# appleii.net
KiCad netlist of a schematic drawn in EAGLE
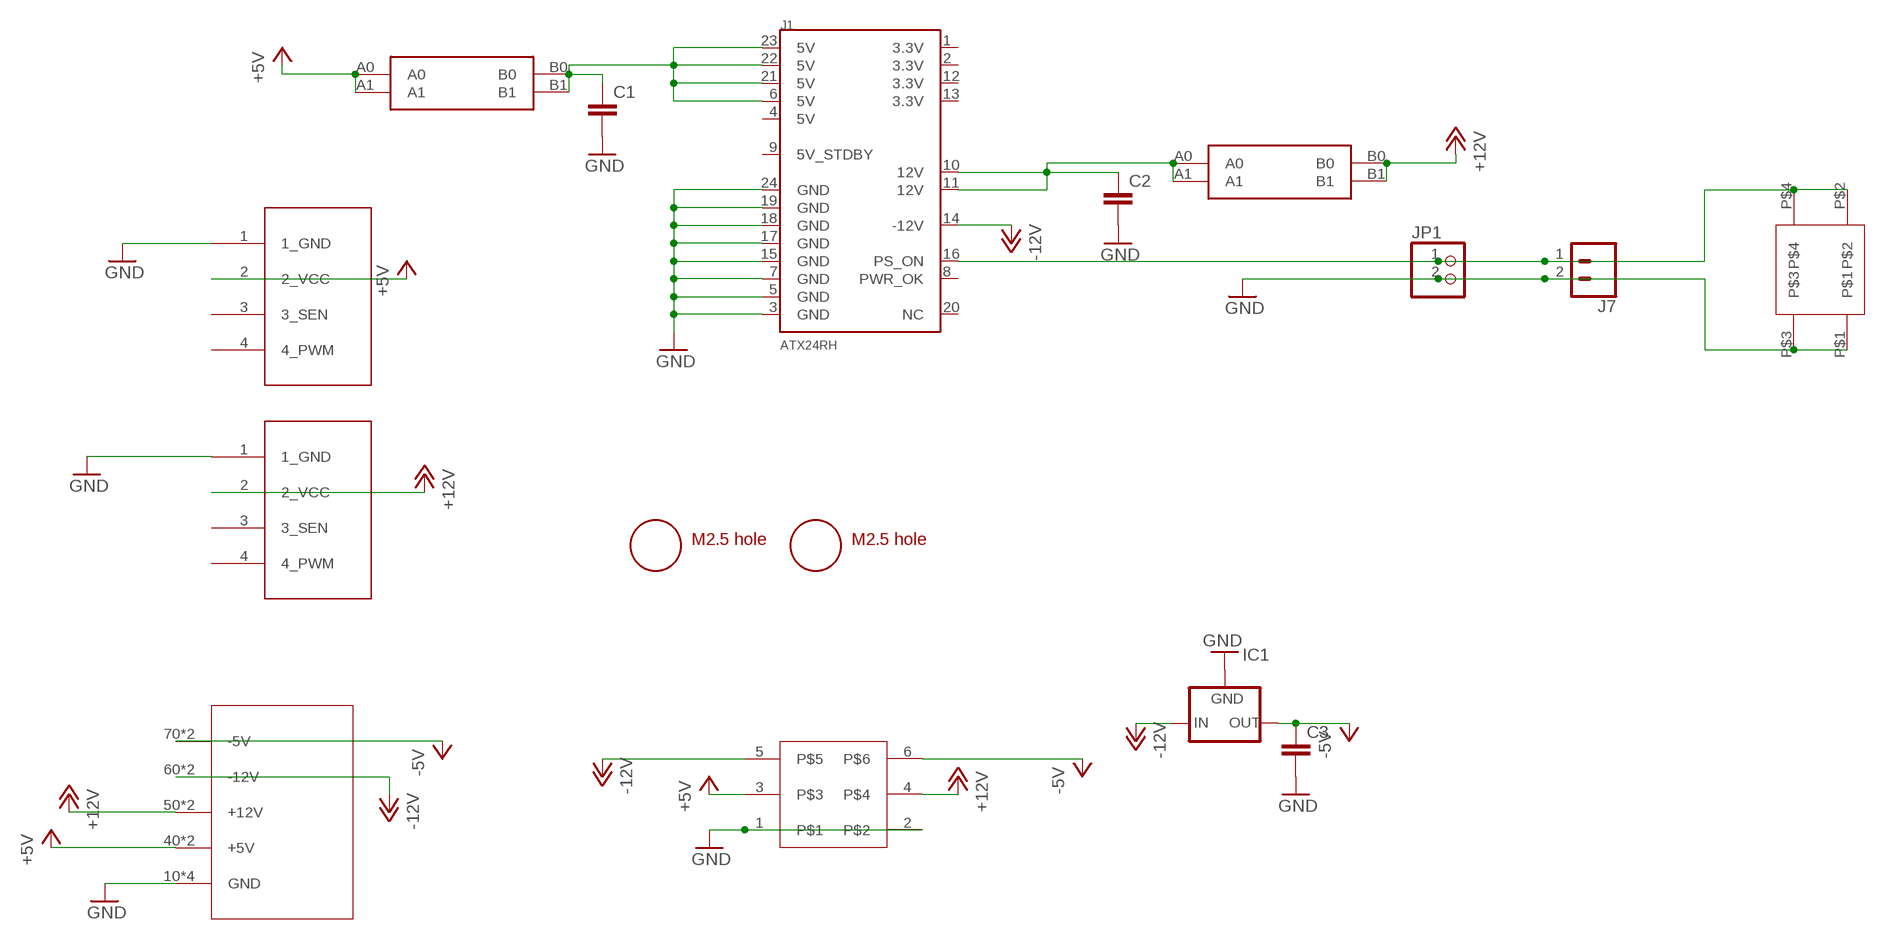
[diagram p0: schematic, sheet 1]

(export (version "E")
  (design (tool "Eeschema 10.0.6"))
  (components
    (comp (ref "C1")
      (value "C5/2.5")
      (footprint "eagle-import:C5B2.5")
      (libsource (lib "eagle-import") (part "C5/2.5"))
    )
    (comp (ref "C2")
      (value "C5/2.5")
      (footprint "eagle-import:C5B2.5")
      (libsource (lib "eagle-import") (part "C5/2.5"))
    )
    (comp (ref "C3")
      (value "C5/2.5")
      (footprint "eagle-import:C5B2.5")
      (libsource (lib "eagle-import") (part "C5/2.5"))
    )
    (comp (ref "IC1")
      (value "79XXS")
      (footprint "eagle-import:79XXS")
      (libsource (lib "eagle-import") (part "79XXS"))
    )
    (comp (ref "J1")
      (value "ATX24RH")
      (footprint "eagle-import:ATX24_RIGHT_ANGLE")
      (libsource (lib "eagle-import") (part "ATX24RH"))
    )
    (comp (ref "J7")
      (value "CONN_023.5MM-NO_SILK")
      (footprint "eagle-import:SCREWTERMINAL-3.5MM-2-NS")
      (libsource (lib "eagle-import") (part "CONN_023.5MM-NO_SILK"))
    )
    (comp (ref "JP1")
      (value "PINHD-1X2")
      (footprint "eagle-import:1X02")
      (libsource (lib "eagle-import") (part "PINHD-1X2"))
    )
    (comp (ref "JP3")
      (value "4PIN_FAN")
      (footprint "eagle-import:1X04")
      (libsource (lib "eagle-import") (part "4PIN_FAN"))
    )
    (comp (ref "JP4")
      (value "4PIN_FAN")
      (footprint "eagle-import:1X04")
      (libsource (lib "eagle-import") (part "4PIN_FAN"))
    )
    (comp (ref "U$1")
      (value "CAR_FUSE_HOLDER3IN1")
      (footprint "eagle-import:FUSE_HOLDER_3IN1")
      (libsource (lib "eagle-import") (part "CAR_FUSE_HOLDER3IN1"))
    )
    (comp (ref "U$2")
      (value "CAR_FUSE_HOLDER3IN1")
      (footprint "eagle-import:FUSE_HOLDER_3IN1")
      (libsource (lib "eagle-import") (part "CAR_FUSE_HOLDER3IN1"))
    )
    (comp (ref "U$3")
      (value "ROCK_SW")
      (footprint "eagle-import:ROCK_SWITCH")
      (libsource (lib "eagle-import") (part "ROCK_SW"))
    )
    (comp (ref "U$4")
      (value "M2.5_MOUNTING_HOLE")
      (footprint "eagle-import:M3_MOUNTING_HOLE_PACK")
      (libsource (lib "eagle-import") (part "M2.5_MOUNTING_HOLE"))
    )
    (comp (ref "U$5")
      (value "M2.5_MOUNTING_HOLE")
      (footprint "eagle-import:M3_MOUNTING_HOLE_PACK")
      (libsource (lib "eagle-import") (part "M2.5_MOUNTING_HOLE"))
    )
    (comp (ref "U$6")
      (value "APPLEII")
      (footprint "eagle-import:APPLEII")
      (libsource (lib "eagle-import") (part "APPLEII"))
    )
    (comp (ref "U$7")
      (value "3.96_FEM_IIGS")
      (footprint "eagle-import:3.96_FEMALE_IIGS_GAP")
      (libsource (lib "eagle-import") (part "3.96_FEM_IIGS"))
    )
  )
  (nets
    (net (code "1") (name "+5V") (class "Default")
      (node (ref "JP4") (pin "2") (pinfunction "2_VCC_2") (pintype "passive"))
      (node (ref "U$1") (pin "A0") (pinfunction "A0_A0") (pintype "bidirectional"))
      (node (ref "U$1") (pin "A1") (pinfunction "A1_A1") (pintype "bidirectional"))
      (node (ref "U$6") (pin "3") (pinfunction "P$3_3") (pintype "bidirectional"))
      (node (ref "U$7") (pin "40") (pinfunction "+5V_40") (pintype "bidirectional"))
      (node (ref "U$7") (pin "41") (pinfunction "+5V_41") (pintype "bidirectional"))
    )
    (net (code "2") (name "+12V") (class "Default")
      (node (ref "JP3") (pin "2") (pinfunction "2_VCC_2") (pintype "passive"))
      (node (ref "U$2") (pin "B0") (pinfunction "B0_B0") (pintype "bidirectional"))
      (node (ref "U$2") (pin "B1") (pinfunction "B1_B1") (pintype "bidirectional"))
      (node (ref "U$6") (pin "4") (pinfunction "P$4_4") (pintype "bidirectional"))
      (node (ref "U$7") (pin "50") (pinfunction "+12V_50") (pintype "bidirectional"))
      (node (ref "U$7") (pin "51") (pinfunction "+12V_51") (pintype "bidirectional"))
    )
    (net (code "3") (name "-5V") (class "Default")
      (node (ref "C3") (pin "1") (pinfunction "1_1") (pintype "passive"))
      (node (ref "IC1") (pin "OUT") (pinfunction "OUT_OUT") (pintype "passive"))
      (node (ref "U$6") (pin "6") (pinfunction "P$6_6") (pintype "bidirectional"))
      (node (ref "U$7") (pin "70") (pinfunction "-5V_70") (pintype "bidirectional"))
      (node (ref "U$7") (pin "71") (pinfunction "-5V_71") (pintype "bidirectional"))
    )
    (net (code "4") (name "-12V") (class "Default")
      (node (ref "IC1") (pin "IN") (pinfunction "IN_IN") (pintype "input"))
      (node (ref "J1") (pin "14") (pinfunction "-12V_14") (pintype "bidirectional"))
      (node (ref "U$6") (pin "5") (pinfunction "P$5_5") (pintype "bidirectional"))
      (node (ref "U$7") (pin "60") (pinfunction "-12V_60") (pintype "bidirectional"))
      (node (ref "U$7") (pin "61") (pinfunction "-12V_61") (pintype "bidirectional"))
    )
    (net (code "5") (name "GND") (class "Default")
      (node (ref "C1") (pin "2") (pinfunction "2_2") (pintype "passive"))
      (node (ref "C2") (pin "2") (pinfunction "2_2") (pintype "passive"))
      (node (ref "C3") (pin "2") (pinfunction "2_2") (pintype "passive"))
      (node (ref "IC1") (pin "GND") (pinfunction "GND_GND") (pintype "input"))
      (node (ref "J1") (pin "15") (pinfunction "GND_15") (pintype "bidirectional"))
      (node (ref "J1") (pin "17") (pinfunction "GND_17") (pintype "bidirectional"))
      (node (ref "J1") (pin "18") (pinfunction "GND_18") (pintype "bidirectional"))
      (node (ref "J1") (pin "19") (pinfunction "GND_19") (pintype "bidirectional"))
      (node (ref "J1") (pin "24") (pinfunction "GND_24") (pintype "bidirectional"))
      (node (ref "J1") (pin "3") (pinfunction "GND_3") (pintype "bidirectional"))
      (node (ref "J1") (pin "5") (pinfunction "GND_5") (pintype "bidirectional"))
      (node (ref "J1") (pin "7") (pinfunction "GND_7") (pintype "bidirectional"))
      (node (ref "J7") (pin "2") (pinfunction "2_2") (pintype "passive"))
      (node (ref "JP1") (pin "2") (pinfunction "2_2") (pintype "passive"))
      (node (ref "JP3") (pin "1") (pinfunction "1_GND_1") (pintype "passive"))
      (node (ref "JP4") (pin "1") (pinfunction "1_GND_1") (pintype "passive"))
      (node (ref "U$3") (pin "P$1") (pinfunction "P$1_P$1") (pintype "bidirectional"))
      (node (ref "U$3") (pin "P$3") (pinfunction "P$3_P$3") (pintype "bidirectional"))
      (node (ref "U$6") (pin "1") (pinfunction "P$1_1") (pintype "bidirectional"))
      (node (ref "U$6") (pin "2") (pinfunction "P$2_2") (pintype "bidirectional"))
      (node (ref "U$7") (pin "10") (pinfunction "GND_10") (pintype "bidirectional"))
      (node (ref "U$7") (pin "11") (pinfunction "GND_11") (pintype "bidirectional"))
      (node (ref "U$7") (pin "20") (pinfunction "GND_20") (pintype "bidirectional"))
      (node (ref "U$7") (pin "21") (pinfunction "GND_21") (pintype "bidirectional"))
    )
    (net (code "6") (name "Net-(C1-Pad1)") (class "Default")
      (node (ref "C1") (pin "1") (pinfunction "1_1") (pintype "passive"))
      (node (ref "J1") (pin "21") (pinfunction "5V_21") (pintype "bidirectional"))
      (node (ref "J1") (pin "22") (pinfunction "5V_22") (pintype "bidirectional"))
      (node (ref "J1") (pin "23") (pinfunction "5V_23") (pintype "bidirectional"))
      (node (ref "J1") (pin "6") (pinfunction "5V_6") (pintype "bidirectional"))
      (node (ref "U$1") (pin "B0") (pinfunction "B0_B0") (pintype "bidirectional"))
      (node (ref "U$1") (pin "B1") (pinfunction "B1_B1") (pintype "bidirectional"))
    )
    (net (code "7") (name "Net-(C2-Pad1)") (class "Default")
      (node (ref "C2") (pin "1") (pinfunction "1_1") (pintype "passive"))
      (node (ref "J1") (pin "10") (pinfunction "12V_10") (pintype "bidirectional"))
      (node (ref "J1") (pin "11") (pinfunction "12V_11") (pintype "bidirectional"))
      (node (ref "U$2") (pin "A0") (pinfunction "A0_A0") (pintype "bidirectional"))
      (node (ref "U$2") (pin "A1") (pinfunction "A1_A1") (pintype "bidirectional"))
    )
    (net (code "8") (name "Net-(J1-PS_ON)") (class "Default")
      (node (ref "J1") (pin "16") (pinfunction "PS_ON_16") (pintype "bidirectional"))
      (node (ref "J7") (pin "1") (pinfunction "1_1") (pintype "passive"))
      (node (ref "JP1") (pin "1") (pinfunction "1_1") (pintype "passive"))
      (node (ref "U$3") (pin "P$2") (pinfunction "P$2_P$2") (pintype "bidirectional"))
      (node (ref "U$3") (pin "P$4") (pinfunction "P$4_P$4") (pintype "bidirectional"))
    )
    (net (code "9") (name "unconnected-(J1-3.3V-Pad1)") (class "Default")
      (node (ref "J1") (pin "1") (pinfunction "3.3V_1") (pintype "bidirectional"))
    )
    (net (code "10") (name "unconnected-(J1-3.3V-Pad2)") (class "Default")
      (node (ref "J1") (pin "2") (pinfunction "3.3V_2") (pintype "bidirectional"))
    )
    (net (code "11") (name "unconnected-(J1-3.3V-Pad12)") (class "Default")
      (node (ref "J1") (pin "12") (pinfunction "3.3V_12") (pintype "bidirectional"))
    )
    (net (code "12") (name "unconnected-(J1-3.3V-Pad13)") (class "Default")
      (node (ref "J1") (pin "13") (pinfunction "3.3V_13") (pintype "bidirectional"))
    )
    (net (code "13") (name "unconnected-(J1-5V-Pad4)") (class "Default")
      (node (ref "J1") (pin "4") (pinfunction "5V_4") (pintype "bidirectional"))
    )
    (net (code "14") (name "unconnected-(J1-5V_STDBY-Pad9)") (class "Default")
      (node (ref "J1") (pin "9") (pinfunction "5V_STDBY_9") (pintype "bidirectional"))
    )
    (net (code "15") (name "unconnected-(J1-NC-Pad20)") (class "Default")
      (node (ref "J1") (pin "20") (pinfunction "NC_20") (pintype "bidirectional"))
    )
    (net (code "16") (name "unconnected-(J1-PWR_OK-Pad8)") (class "Default")
      (node (ref "J1") (pin "8") (pinfunction "PWR_OK_8") (pintype "bidirectional"))
    )
    (net (code "17") (name "unconnected-(JP3-3_SEN-Pad3)") (class "Default")
      (node (ref "JP3") (pin "3") (pinfunction "3_SEN_3") (pintype "passive"))
    )
    (net (code "18") (name "unconnected-(JP3-4_PWM-Pad4)") (class "Default")
      (node (ref "JP3") (pin "4") (pinfunction "4_PWM_4") (pintype "passive"))
    )
    (net (code "19") (name "unconnected-(JP4-3_SEN-Pad3)") (class "Default")
      (node (ref "JP4") (pin "3") (pinfunction "3_SEN_3") (pintype "passive"))
    )
    (net (code "20") (name "unconnected-(JP4-4_PWM-Pad4)") (class "Default")
      (node (ref "JP4") (pin "4") (pinfunction "4_PWM_4") (pintype "passive"))
    )
  )
)
